# OpenPLCv0_2_0_AnalogueInput.net
KiCad netlist of a schematic drawn in Altium Designer
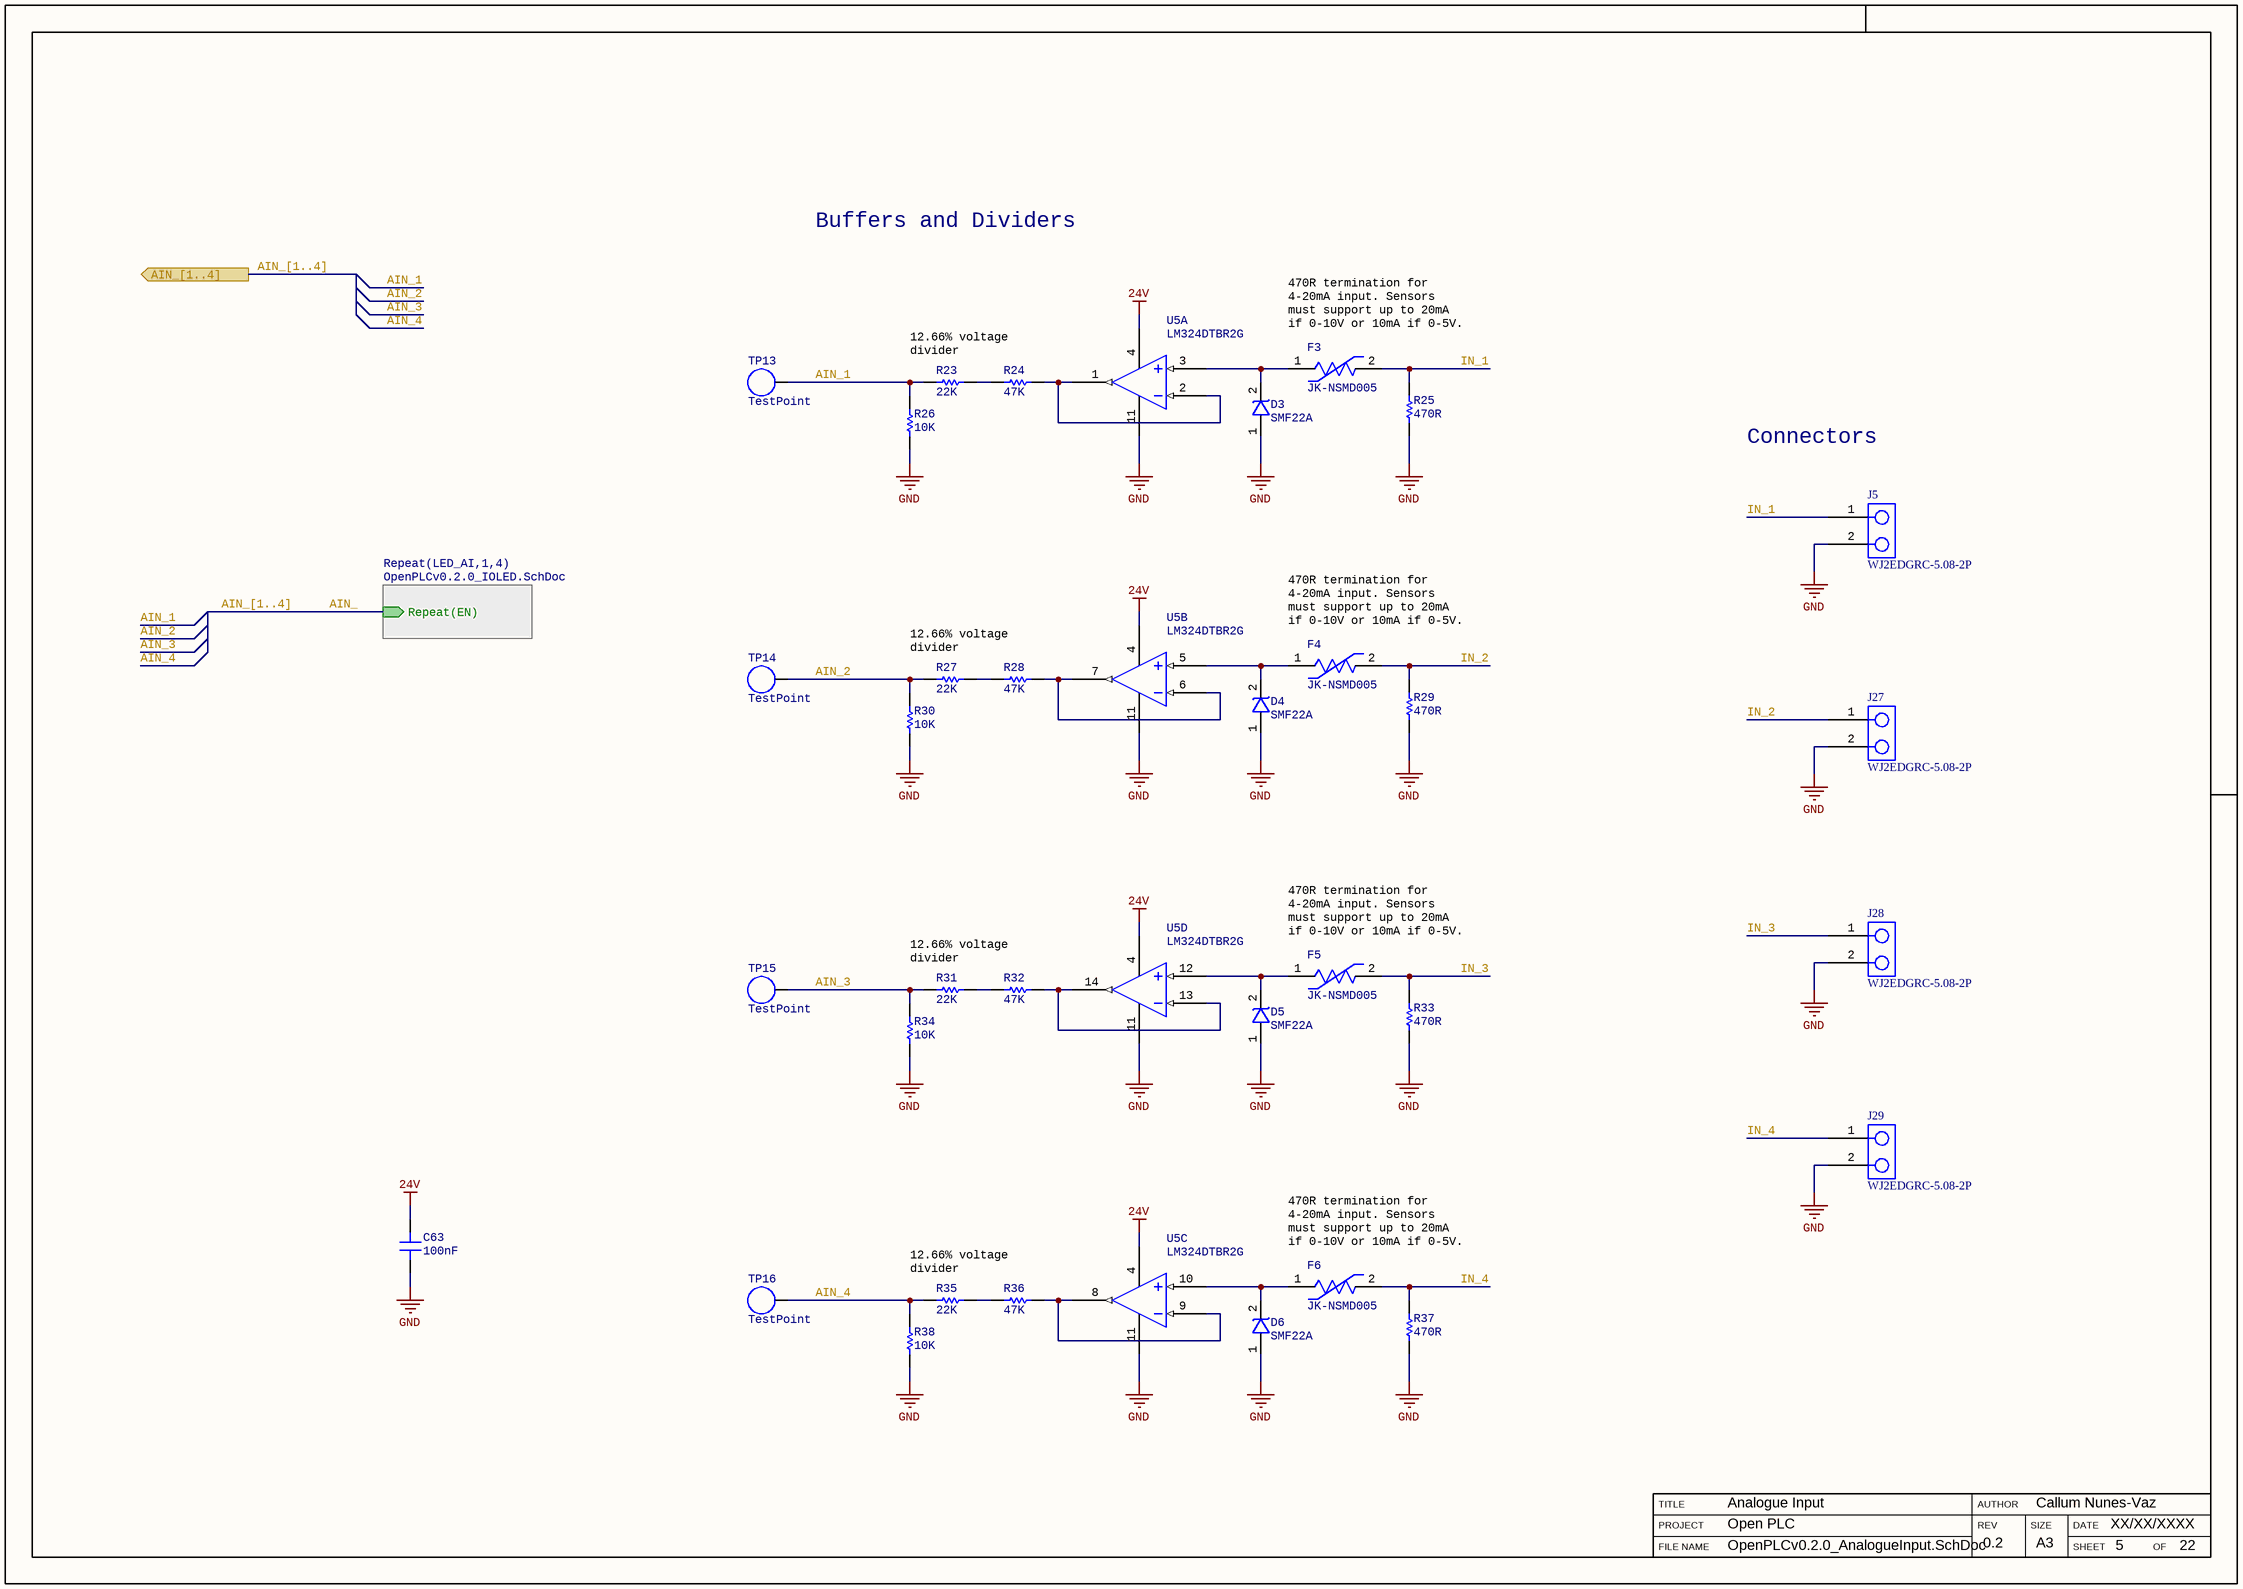
[diagram p0: OpenPLCv0.2.0_AnalogueInput.SchDoc]

(export (version "E")
  (design (tool "Eeschema 10.0.6"))
  (components
    (comp (ref "C63")
      (value "CC0402KRX5R9BB104")
      (footprint "SMD_CAP_0402(1005)_N")
      (description "100nF ±10% 50V X5R 0402 Multilayer Ceramic Capacitors MLCC - SMD/SMT RoHS")
      (fields (field (name "TOLERANCE") "10%") (field (name "CAPACITANCE") "100nF"))
      (libsource (lib "BrauV2_Capacitor") (part "100nF 0402 50V 10%"))
    )
    (comp (ref "D3")
      (value "SMF22A")
      (footprint "SOD-123FL")
      (description "Unidirectional 22V 24.4V 35.5V 5.6A SOD-123F TVS RoHS")
      (libsource (lib "BrauV2") (part "SMF22A"))
    )
    (comp (ref "D4")
      (value "SMF22A")
      (footprint "SOD-123FL")
      (description "Unidirectional 22V 24.4V 35.5V 5.6A SOD-123F TVS RoHS")
      (libsource (lib "BrauV2") (part "SMF22A"))
    )
    (comp (ref "D5")
      (value "SMF22A")
      (footprint "SOD-123FL")
      (description "Unidirectional 22V 24.4V 35.5V 5.6A SOD-123F TVS RoHS")
      (libsource (lib "BrauV2") (part "SMF22A"))
    )
    (comp (ref "D6")
      (value "SMF22A")
      (footprint "SOD-123FL")
      (description "Unidirectional 22V 24.4V 35.5V 5.6A SOD-123F TVS RoHS")
      (libsource (lib "BrauV2") (part "SMF22A"))
    )
    (comp (ref "F3")
      (value "JK-NSMD005")
      (footprint "SMD_RES_1206(3216)_N")
      (description "60V 150mA 1.5s 1206 PTC Resettable Fuses RoHS")
      (libsource (lib "BrauV2_Resistor") (part "JK-NSMD005"))
    )
    (comp (ref "F4")
      (value "JK-NSMD005")
      (footprint "SMD_RES_1206(3216)_N")
      (description "60V 150mA 1.5s 1206 PTC Resettable Fuses RoHS")
      (libsource (lib "BrauV2_Resistor") (part "JK-NSMD005"))
    )
    (comp (ref "F5")
      (value "JK-NSMD005")
      (footprint "SMD_RES_1206(3216)_N")
      (description "60V 150mA 1.5s 1206 PTC Resettable Fuses RoHS")
      (libsource (lib "BrauV2_Resistor") (part "JK-NSMD005"))
    )
    (comp (ref "F6")
      (value "JK-NSMD005")
      (footprint "SMD_RES_1206(3216)_N")
      (description "60V 150mA 1.5s 1206 PTC Resettable Fuses RoHS")
      (libsource (lib "BrauV2_Resistor") (part "JK-NSMD005"))
    )
    (comp (ref "J5")
      (value "WJ2EDGRC-5.08-2P")
      (footprint "796638-2_BoardEdgeAlt")
      (description "Covered（4Sided） 2 1 0.200\"（5.08mm） 2 P=5.08mm Pluggable System Terminal Block RoHS")
      (libsource (lib "OpenPLCv0.2.0_Connector") (part "WJ2EDGRC-5.08-2P"))
    )
    (comp (ref "J27")
      (value "WJ2EDGRC-5.08-2P")
      (footprint "796638-2_BoardEdgeAlt")
      (description "Covered（4Sided） 2 1 0.200\"（5.08mm） 2 P=5.08mm Pluggable System Terminal Block RoHS")
      (libsource (lib "OpenPLCv0.2.0_Connector") (part "WJ2EDGRC-5.08-2P"))
    )
    (comp (ref "J28")
      (value "WJ2EDGRC-5.08-2P")
      (footprint "796638-2_BoardEdgeAlt")
      (description "Covered（4Sided） 2 1 0.200\"（5.08mm） 2 P=5.08mm Pluggable System Terminal Block RoHS")
      (libsource (lib "OpenPLCv0.2.0_Connector") (part "WJ2EDGRC-5.08-2P"))
    )
    (comp (ref "J29")
      (value "WJ2EDGRC-5.08-2P")
      (footprint "796638-2_BoardEdgeAlt")
      (description "Covered（4Sided） 2 1 0.200\"（5.08mm） 2 P=5.08mm Pluggable System Terminal Block RoHS")
      (libsource (lib "OpenPLCv0.2.0_Connector") (part "WJ2EDGRC-5.08-2P"))
    )
    (comp (ref "R23")
      (value "RC0402FR-0722KL")
      (footprint "SMD_RES_0402(1005)_N")
      (description "22kΩ ±1% 1/16W ±100ppm/℃ 0402 Chip Resistor - Surface Mount RoHS")
      (fields (field (name "TOLERANCE") "1%") (field (name "RESISTANCE") "22K"))
      (libsource (lib "BrauV2_Resistor") (part "22K 0402 1% 1/16W"))
    )
    (comp (ref "R24")
      (value "RC0402FR-0747KL")
      (footprint "SMD_RES_0402(1005)_N")
      (description "47kΩ ±1% 1/16W ±100ppm/℃ 0402 Chip Resistor - Surface Mount RoHS")
      (fields (field (name "TOLERANCE") "1%") (field (name "RESISTANCE") "47K"))
      (libsource (lib "BrauV2_Resistor") (part "47K 0402 1% 1/16W"))
    )
    (comp (ref "R25")
      (value "AC2512FK-07470RL")
      (footprint "SMD_RES_2512(6432)_N")
      (description "470Ω ±1% 1W ±100ppm/℃ 2512 Chip Resistor - Surface Mount RoHS")
      (fields (field (name "TOLERANCE") "1%") (field (name "RESISTANCE") "470R"))
      (libsource (lib "BrauV2_Resistor") (part "470R 2512 1% 1W"))
    )
    (comp (ref "R26")
      (value "RC0402FR-0710KL")
      (footprint "SMD_RES_0402(1005)_N")
      (description "10kΩ ±1% 1/16W ±100ppm/℃ 0402 Chip Resistor - Surface Mount RoHS")
      (fields (field (name "TOLERANCE") "1%") (field (name "RESISTANCE") "10K"))
      (libsource (lib "BrauV2_Resistor") (part "10K 0402 1% 1/16W"))
    )
    (comp (ref "R27")
      (value "RC0402FR-0722KL")
      (footprint "SMD_RES_0402(1005)_N")
      (description "22kΩ ±1% 1/16W ±100ppm/℃ 0402 Chip Resistor - Surface Mount RoHS")
      (fields (field (name "TOLERANCE") "1%") (field (name "RESISTANCE") "22K"))
      (libsource (lib "BrauV2_Resistor") (part "22K 0402 1% 1/16W"))
    )
    (comp (ref "R28")
      (value "RC0402FR-0747KL")
      (footprint "SMD_RES_0402(1005)_N")
      (description "47kΩ ±1% 1/16W ±100ppm/℃ 0402 Chip Resistor - Surface Mount RoHS")
      (fields (field (name "TOLERANCE") "1%") (field (name "RESISTANCE") "47K"))
      (libsource (lib "BrauV2_Resistor") (part "47K 0402 1% 1/16W"))
    )
    (comp (ref "R29")
      (value "AC2512FK-07470RL")
      (footprint "SMD_RES_2512(6432)_N")
      (description "470Ω ±1% 1W ±100ppm/℃ 2512 Chip Resistor - Surface Mount RoHS")
      (fields (field (name "TOLERANCE") "1%") (field (name "RESISTANCE") "470R"))
      (libsource (lib "BrauV2_Resistor") (part "470R 2512 1% 1W"))
    )
    (comp (ref "R30")
      (value "RC0402FR-0710KL")
      (footprint "SMD_RES_0402(1005)_N")
      (description "10kΩ ±1% 1/16W ±100ppm/℃ 0402 Chip Resistor - Surface Mount RoHS")
      (fields (field (name "TOLERANCE") "1%") (field (name "RESISTANCE") "10K"))
      (libsource (lib "BrauV2_Resistor") (part "10K 0402 1% 1/16W"))
    )
    (comp (ref "R31")
      (value "RC0402FR-0722KL")
      (footprint "SMD_RES_0402(1005)_N")
      (description "22kΩ ±1% 1/16W ±100ppm/℃ 0402 Chip Resistor - Surface Mount RoHS")
      (fields (field (name "TOLERANCE") "1%") (field (name "RESISTANCE") "22K"))
      (libsource (lib "BrauV2_Resistor") (part "22K 0402 1% 1/16W"))
    )
    (comp (ref "R32")
      (value "RC0402FR-0747KL")
      (footprint "SMD_RES_0402(1005)_N")
      (description "47kΩ ±1% 1/16W ±100ppm/℃ 0402 Chip Resistor - Surface Mount RoHS")
      (fields (field (name "TOLERANCE") "1%") (field (name "RESISTANCE") "47K"))
      (libsource (lib "BrauV2_Resistor") (part "47K 0402 1% 1/16W"))
    )
    (comp (ref "R33")
      (value "AC2512FK-07470RL")
      (footprint "SMD_RES_2512(6432)_N")
      (description "470Ω ±1% 1W ±100ppm/℃ 2512 Chip Resistor - Surface Mount RoHS")
      (fields (field (name "TOLERANCE") "1%") (field (name "RESISTANCE") "470R"))
      (libsource (lib "BrauV2_Resistor") (part "470R 2512 1% 1W"))
    )
    (comp (ref "R34")
      (value "RC0402FR-0710KL")
      (footprint "SMD_RES_0402(1005)_N")
      (description "10kΩ ±1% 1/16W ±100ppm/℃ 0402 Chip Resistor - Surface Mount RoHS")
      (fields (field (name "TOLERANCE") "1%") (field (name "RESISTANCE") "10K"))
      (libsource (lib "BrauV2_Resistor") (part "10K 0402 1% 1/16W"))
    )
    (comp (ref "R35")
      (value "RC0402FR-0722KL")
      (footprint "SMD_RES_0402(1005)_N")
      (description "22kΩ ±1% 1/16W ±100ppm/℃ 0402 Chip Resistor - Surface Mount RoHS")
      (fields (field (name "TOLERANCE") "1%") (field (name "RESISTANCE") "22K"))
      (libsource (lib "BrauV2_Resistor") (part "22K 0402 1% 1/16W"))
    )
    (comp (ref "R36")
      (value "RC0402FR-0747KL")
      (footprint "SMD_RES_0402(1005)_N")
      (description "47kΩ ±1% 1/16W ±100ppm/℃ 0402 Chip Resistor - Surface Mount RoHS")
      (fields (field (name "TOLERANCE") "1%") (field (name "RESISTANCE") "47K"))
      (libsource (lib "BrauV2_Resistor") (part "47K 0402 1% 1/16W"))
    )
    (comp (ref "R37")
      (value "AC2512FK-07470RL")
      (footprint "SMD_RES_2512(6432)_N")
      (description "470Ω ±1% 1W ±100ppm/℃ 2512 Chip Resistor - Surface Mount RoHS")
      (fields (field (name "TOLERANCE") "1%") (field (name "RESISTANCE") "470R"))
      (libsource (lib "BrauV2_Resistor") (part "470R 2512 1% 1W"))
    )
    (comp (ref "R38")
      (value "RC0402FR-0710KL")
      (footprint "SMD_RES_0402(1005)_N")
      (description "10kΩ ±1% 1/16W ±100ppm/℃ 0402 Chip Resistor - Surface Mount RoHS")
      (fields (field (name "TOLERANCE") "1%") (field (name "RESISTANCE") "10K"))
      (libsource (lib "BrauV2_Resistor") (part "10K 0402 1% 1/16W"))
    )
    (comp (ref "TP13")
      (value "TestPoint")
      (footprint "Pad")
      (libsource (lib "OpenPLCv0.2.0_Misc") (part "Test point"))
    )
    (comp (ref "TP14")
      (value "TestPoint")
      (footprint "Pad")
      (libsource (lib "OpenPLCv0.2.0_Misc") (part "Test point"))
    )
    (comp (ref "TP15")
      (value "TestPoint")
      (footprint "Pad")
      (libsource (lib "OpenPLCv0.2.0_Misc") (part "Test point"))
    )
    (comp (ref "TP16")
      (value "TestPoint")
      (footprint "Pad")
      (libsource (lib "OpenPLCv0.2.0_Misc") (part "Test point"))
    )
    (comp (ref "U5")
      (value "LM324DTBR2G")
      (footprint "TSSOP-14")
      (description "General Purpose 4 3V ~ 32V, ±1.5V ~ 16V 1MHz 0.6 V/us TSSOP-14 Operational Amplifiers RoHS")
      (libsource (lib "BrauV2_IC") (part "LM324DTBR2G"))
    )
  )
  (nets
    (net (code "2") (name "/AIN_1") (class "Default")
      (node (ref "R23") (pin "1") (pinfunction "1_1") (pintype "passive"))
      (node (ref "R26") (pin "1") (pinfunction "1_1") (pintype "passive"))
      (node (ref "TP13") (pin "1") (pinfunction "1_1") (pintype "passive"))
    )
    (net (code "3") (name "/AIN_2") (class "Default")
      (node (ref "R27") (pin "1") (pinfunction "1_1") (pintype "passive"))
      (node (ref "R30") (pin "1") (pinfunction "1_1") (pintype "passive"))
      (node (ref "TP14") (pin "1") (pinfunction "1_1") (pintype "passive"))
    )
    (net (code "4") (name "/AIN_3") (class "Default")
      (node (ref "R31") (pin "1") (pinfunction "1_1") (pintype "passive"))
      (node (ref "R34") (pin "1") (pinfunction "1_1") (pintype "passive"))
      (node (ref "TP15") (pin "1") (pinfunction "1_1") (pintype "passive"))
    )
    (net (code "5") (name "/AIN_4") (class "Default")
      (node (ref "R35") (pin "1") (pinfunction "1_1") (pintype "passive"))
      (node (ref "R38") (pin "1") (pinfunction "1_1") (pintype "passive"))
      (node (ref "TP16") (pin "1") (pinfunction "1_1") (pintype "passive"))
    )
    (net (code "7") (name "/IN_1") (class "Default")
      (node (ref "F3") (pin "2") (pinfunction "2_2") (pintype "passive"))
      (node (ref "J5") (pin "1") (pinfunction "1_1") (pintype "passive"))
      (node (ref "R25") (pin "2") (pinfunction "2_2") (pintype "passive"))
    )
    (net (code "8") (name "/IN_2") (class "Default")
      (node (ref "F4") (pin "2") (pinfunction "2_2") (pintype "passive"))
      (node (ref "J27") (pin "1") (pinfunction "1_1") (pintype "passive"))
      (node (ref "R29") (pin "2") (pinfunction "2_2") (pintype "passive"))
    )
    (net (code "9") (name "/IN_3") (class "Default")
      (node (ref "F5") (pin "2") (pinfunction "2_2") (pintype "passive"))
      (node (ref "J28") (pin "1") (pinfunction "1_1") (pintype "passive"))
      (node (ref "R33") (pin "2") (pinfunction "2_2") (pintype "passive"))
    )
    (net (code "10") (name "/IN_4") (class "Default")
      (node (ref "F6") (pin "2") (pinfunction "2_2") (pintype "passive"))
      (node (ref "J29") (pin "1") (pinfunction "1_1") (pintype "passive"))
      (node (ref "R37") (pin "2") (pinfunction "2_2") (pintype "passive"))
    )
    (net (code "11") (name "24V") (class "Default")
      (node (ref "C63") (pin "2") (pinfunction "2_2") (pintype "passive"))
      (node (ref "U5") (pin "4") (pinfunction "VDD_4") (pintype "power_in"))
    )
    (net (code "12") (name "GND") (class "Default")
      (node (ref "C63") (pin "1") (pinfunction "1_1") (pintype "passive"))
      (node (ref "D3") (pin "1") (pinfunction "ANODE_1") (pintype "passive"))
      (node (ref "D4") (pin "1") (pinfunction "ANODE_1") (pintype "passive"))
      (node (ref "D5") (pin "1") (pinfunction "ANODE_1") (pintype "passive"))
      (node (ref "D6") (pin "1") (pinfunction "ANODE_1") (pintype "passive"))
      (node (ref "J27") (pin "2") (pinfunction "2_2") (pintype "passive"))
      (node (ref "J28") (pin "2") (pinfunction "2_2") (pintype "passive"))
      (node (ref "J29") (pin "2") (pinfunction "2_2") (pintype "passive"))
      (node (ref "J5") (pin "2") (pinfunction "2_2") (pintype "passive"))
      (node (ref "R25") (pin "1") (pinfunction "1_1") (pintype "passive"))
      (node (ref "R26") (pin "2") (pinfunction "2_2") (pintype "passive"))
      (node (ref "R29") (pin "1") (pinfunction "1_1") (pintype "passive"))
      (node (ref "R30") (pin "2") (pinfunction "2_2") (pintype "passive"))
      (node (ref "R33") (pin "1") (pinfunction "1_1") (pintype "passive"))
      (node (ref "R34") (pin "2") (pinfunction "2_2") (pintype "passive"))
      (node (ref "R37") (pin "1") (pinfunction "1_1") (pintype "passive"))
      (node (ref "R38") (pin "2") (pinfunction "2_2") (pintype "passive"))
      (node (ref "U5") (pin "11") (pinfunction "VSS_11") (pintype "power_in"))
    )
    (net (code "13") (name "Net-(D3-CATHODE)") (class "Default")
      (node (ref "D3") (pin "2") (pinfunction "CATHODE_2") (pintype "passive"))
      (node (ref "F3") (pin "1") (pinfunction "1_1") (pintype "passive"))
      (node (ref "U5") (pin "3") (pinfunction "VIN+_3") (pintype "input"))
    )
    (net (code "14") (name "Net-(D4-CATHODE)") (class "Default")
      (node (ref "D4") (pin "2") (pinfunction "CATHODE_2") (pintype "passive"))
      (node (ref "F4") (pin "1") (pinfunction "1_1") (pintype "passive"))
      (node (ref "U5") (pin "5") (pinfunction "VIN+_5") (pintype "input"))
    )
    (net (code "15") (name "Net-(D5-CATHODE)") (class "Default")
      (node (ref "D5") (pin "2") (pinfunction "CATHODE_2") (pintype "passive"))
      (node (ref "F5") (pin "1") (pinfunction "1_1") (pintype "passive"))
      (node (ref "U5") (pin "12") (pinfunction "VIN+_12") (pintype "input"))
    )
    (net (code "16") (name "Net-(D6-CATHODE)") (class "Default")
      (node (ref "D6") (pin "2") (pinfunction "CATHODE_2") (pintype "passive"))
      (node (ref "F6") (pin "1") (pinfunction "1_1") (pintype "passive"))
      (node (ref "U5") (pin "10") (pinfunction "VIN+_10") (pintype "input"))
    )
    (net (code "17") (name "Net-(R23-Pad2)") (class "Default")
      (node (ref "R23") (pin "2") (pinfunction "2_2") (pintype "passive"))
      (node (ref "R24") (pin "2") (pinfunction "2_2") (pintype "passive"))
    )
    (net (code "18") (name "Net-(R27-Pad2)") (class "Default")
      (node (ref "R27") (pin "2") (pinfunction "2_2") (pintype "passive"))
      (node (ref "R28") (pin "2") (pinfunction "2_2") (pintype "passive"))
    )
    (net (code "19") (name "Net-(R31-Pad2)") (class "Default")
      (node (ref "R31") (pin "2") (pinfunction "2_2") (pintype "passive"))
      (node (ref "R32") (pin "2") (pinfunction "2_2") (pintype "passive"))
    )
    (net (code "20") (name "Net-(R35-Pad2)") (class "Default")
      (node (ref "R35") (pin "2") (pinfunction "2_2") (pintype "passive"))
      (node (ref "R36") (pin "2") (pinfunction "2_2") (pintype "passive"))
    )
    (net (code "21") (name "Net-(U5A-VIN-)") (class "Default")
      (node (ref "R24") (pin "1") (pinfunction "1_1") (pintype "passive"))
      (node (ref "U5") (pin "1") (pinfunction "VOUT_1") (pintype "output"))
      (node (ref "U5") (pin "2") (pinfunction "VIN-_2") (pintype "input"))
    )
    (net (code "22") (name "Net-(U5B-VIN-)") (class "Default")
      (node (ref "R28") (pin "1") (pinfunction "1_1") (pintype "passive"))
      (node (ref "U5") (pin "6") (pinfunction "VIN-_6") (pintype "input"))
      (node (ref "U5") (pin "7") (pinfunction "VOUT_7") (pintype "output"))
    )
    (net (code "23") (name "Net-(U5C-VIN-)") (class "Default")
      (node (ref "R36") (pin "1") (pinfunction "1_1") (pintype "passive"))
      (node (ref "U5") (pin "8") (pinfunction "VOUT_8") (pintype "output"))
      (node (ref "U5") (pin "9") (pinfunction "VIN-_9") (pintype "input"))
    )
    (net (code "24") (name "Net-(U5D-VIN-)") (class "Default")
      (node (ref "R32") (pin "1") (pinfunction "1_1") (pintype "passive"))
      (node (ref "U5") (pin "13") (pinfunction "VIN-_13") (pintype "input"))
      (node (ref "U5") (pin "14") (pinfunction "VOUT_14") (pintype "output"))
    )
  )
)
